# OGX360I-2CH.net
KiCad netlist of a schematic drawn in EAGLE
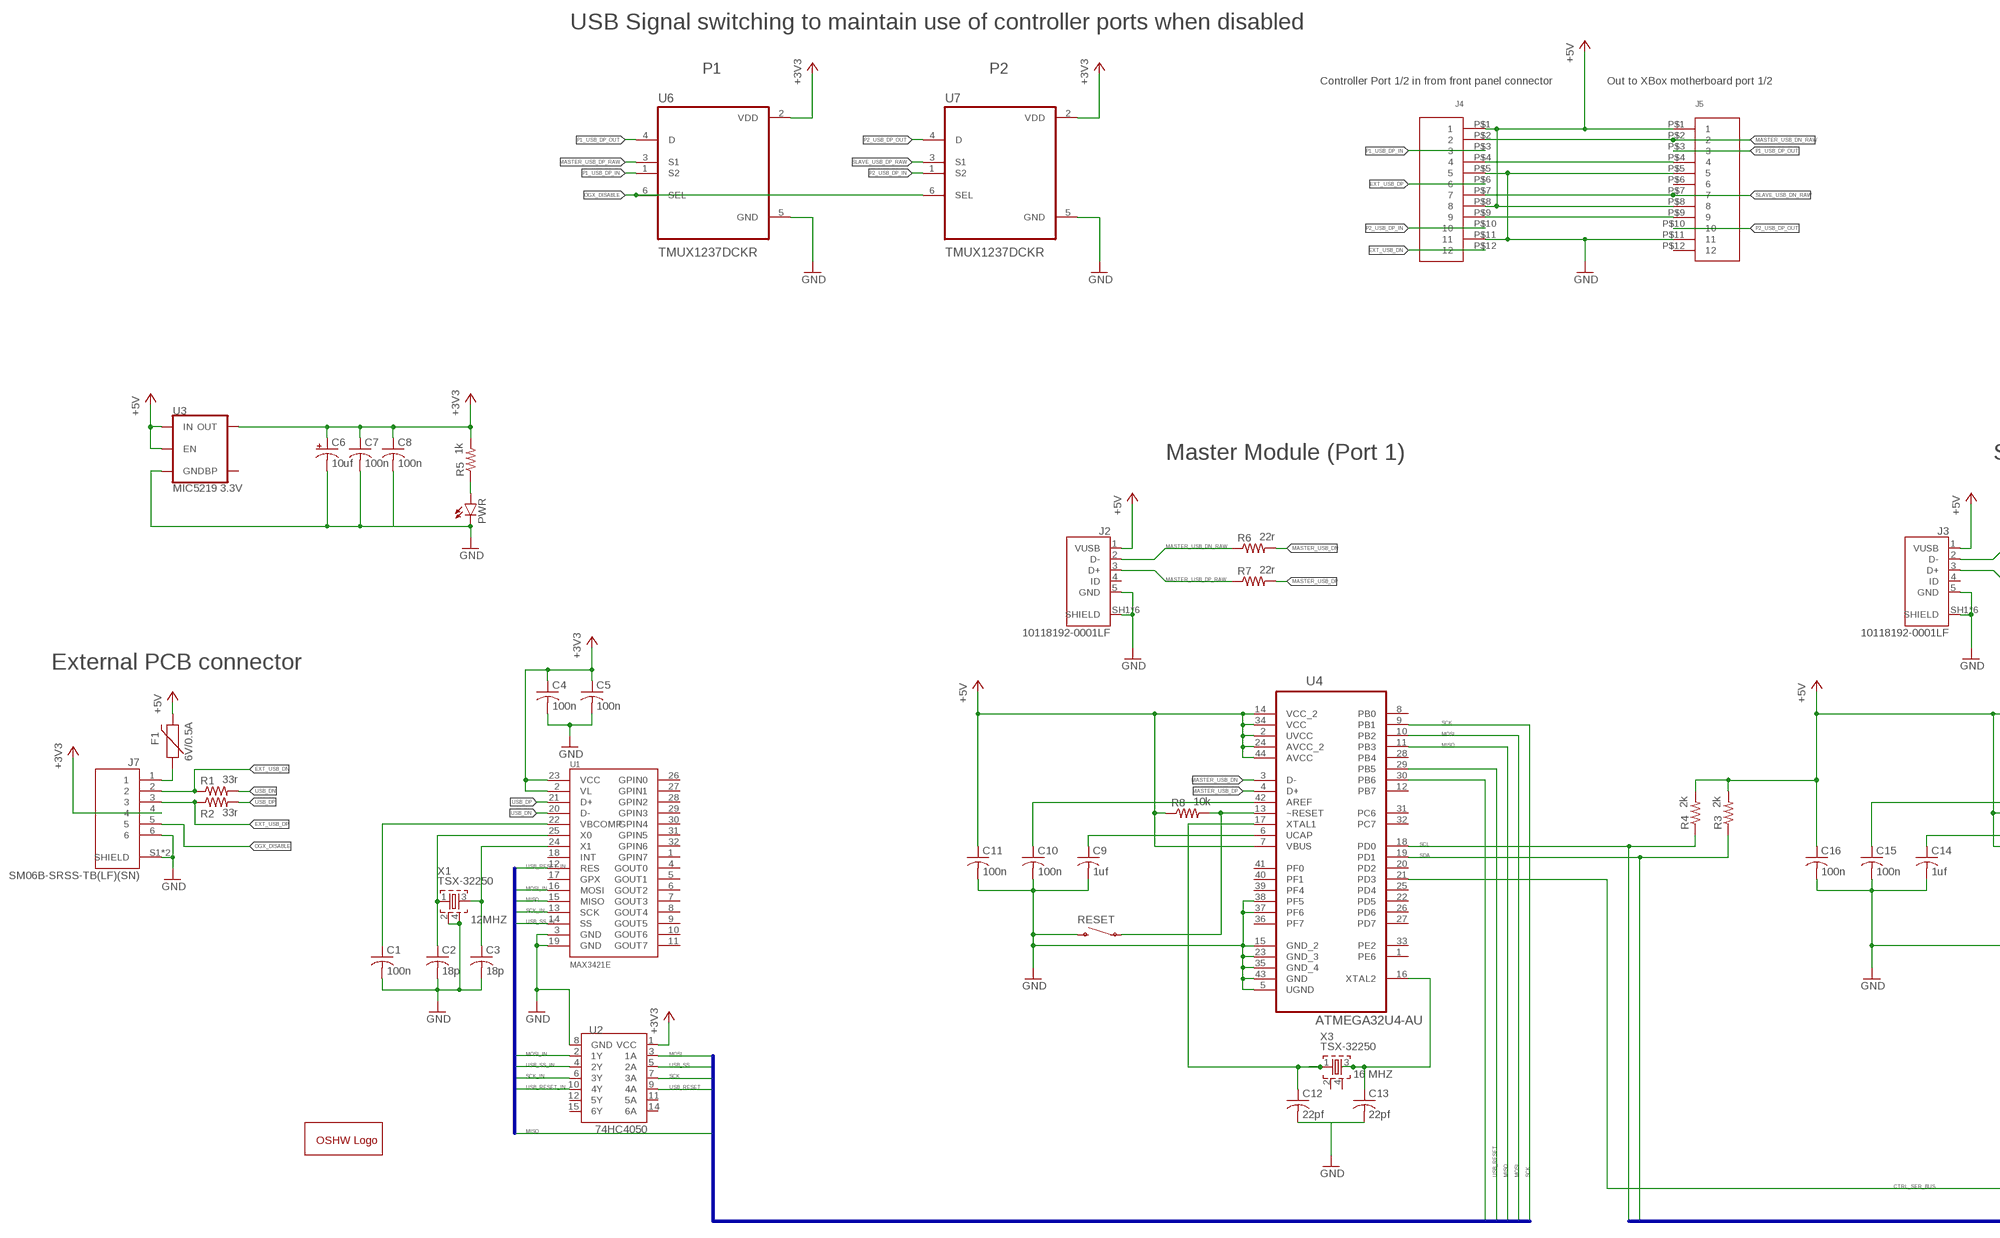
[diagram p0: schematic, sheet 1, part 1 of 2]
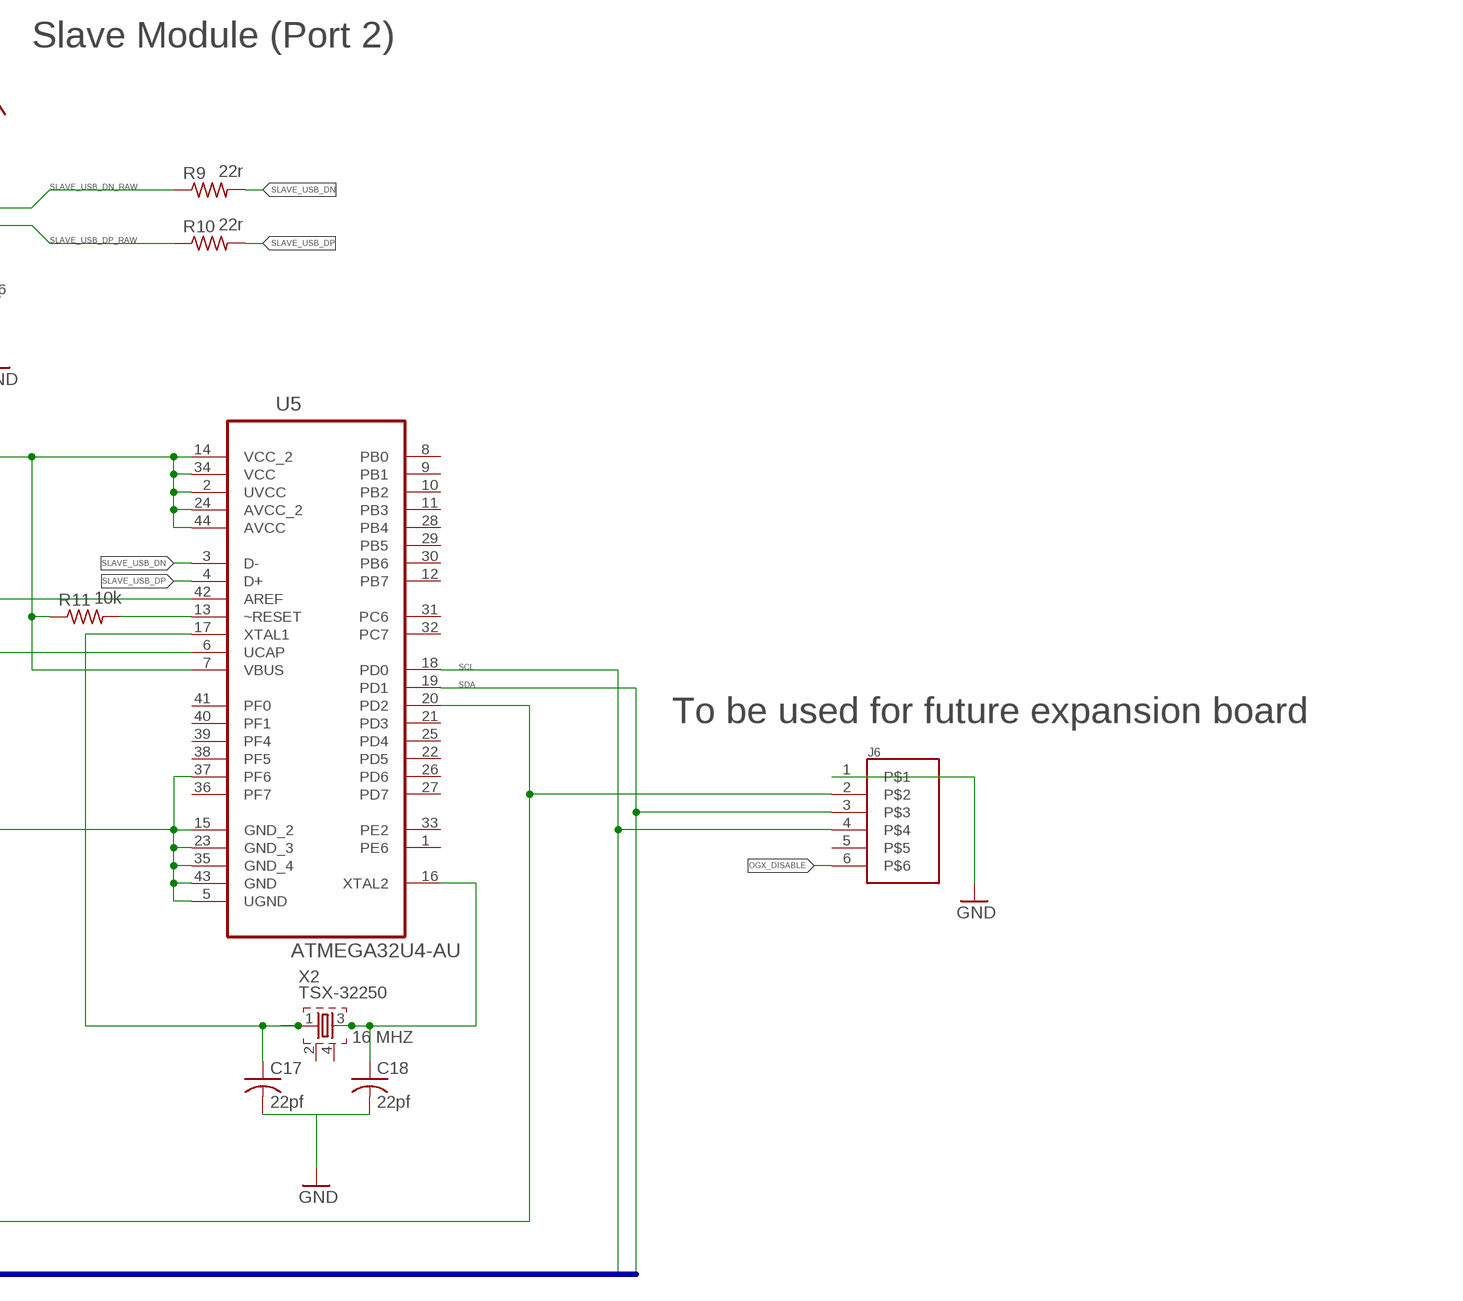
[diagram p1: schematic, sheet 1, part 2 of 2]

(export (version "E")
  (design (tool "Eeschema 10.0.6"))
  (components
    (comp (ref "C1")
      (value "100n")
      (footprint "eagle-import:C0805")
      (libsource (lib "eagle-import") (part "C-USC0805"))
    )
    (comp (ref "C2")
      (value "18p")
      (footprint "eagle-import:C0805")
      (libsource (lib "eagle-import") (part "C-USC0805"))
    )
    (comp (ref "C3")
      (value "18p")
      (footprint "eagle-import:C0805")
      (libsource (lib "eagle-import") (part "C-USC0805"))
    )
    (comp (ref "C4")
      (value "100n")
      (footprint "eagle-import:C0805")
      (libsource (lib "eagle-import") (part "C-USC0805"))
    )
    (comp (ref "C5")
      (value "100n")
      (footprint "eagle-import:C0805")
      (libsource (lib "eagle-import") (part "C-USC0805"))
    )
    (comp (ref "C6")
      (value "10uf")
      (footprint "eagle-import:153CLV-0405")
      (libsource (lib "eagle-import") (part "CPOL-US153CLV-0405"))
    )
    (comp (ref "C7")
      (value "100n")
      (footprint "eagle-import:C0805")
      (libsource (lib "eagle-import") (part "C-USC0805"))
    )
    (comp (ref "C8")
      (value "100n")
      (footprint "eagle-import:C0805")
      (libsource (lib "eagle-import") (part "C-USC0805"))
    )
    (comp (ref "C9")
      (value "1uf")
      (footprint "eagle-import:C0805")
      (libsource (lib "eagle-import") (part "C-USC0805"))
    )
    (comp (ref "C10")
      (value "100n")
      (footprint "eagle-import:C0805")
      (libsource (lib "eagle-import") (part "C-USC0805"))
    )
    (comp (ref "C11")
      (value "100n")
      (footprint "eagle-import:C0805")
      (libsource (lib "eagle-import") (part "C-USC0805"))
    )
    (comp (ref "C12")
      (value "22pf")
      (footprint "eagle-import:C0805")
      (libsource (lib "eagle-import") (part "C-USC0805"))
    )
    (comp (ref "C13")
      (value "22pf")
      (footprint "eagle-import:C0805")
      (libsource (lib "eagle-import") (part "C-USC0805"))
    )
    (comp (ref "C14")
      (value "1uf")
      (footprint "eagle-import:C0805")
      (libsource (lib "eagle-import") (part "C-USC0805"))
    )
    (comp (ref "C15")
      (value "100n")
      (footprint "eagle-import:C0805")
      (libsource (lib "eagle-import") (part "C-USC0805"))
    )
    (comp (ref "C16")
      (value "100n")
      (footprint "eagle-import:C0805")
      (libsource (lib "eagle-import") (part "C-USC0805"))
    )
    (comp (ref "C17")
      (value "22pf")
      (footprint "eagle-import:C0805")
      (libsource (lib "eagle-import") (part "C-USC0805"))
    )
    (comp (ref "C18")
      (value "22pf")
      (footprint "eagle-import:C0805")
      (libsource (lib "eagle-import") (part "C-USC0805"))
    )
    (comp (ref "F1")
      (value "6V/0.5A")
      (footprint "eagle-import:1206")
      (libsource (lib "eagle-import") (part "PPTC_HALF-AMP"))
    )
    (comp (ref "GOLD_ORB_SM1")
      (value "OSHWLOGOLOGO8MM")
      (footprint "eagle-import:OSHW_8MM")
      (libsource (lib "eagle-import") (part "OSHWLOGOLOGO8MM"))
    )
    (comp (ref "J2")
      (value "10118192-0001LF")
      (footprint "eagle-import:AMPHENOL_10118192-0001LF")
      (fields (field (name "MF") "Amphenol ICC (FCI)"))
      (libsource (lib "eagle-import") (part "10118192-0001LF"))
    )
    (comp (ref "J3")
      (value "10118192-0001LF")
      (footprint "eagle-import:AMPHENOL_10118192-0001LF")
      (fields (field (name "MF") "Amphenol ICC (FCI)"))
      (libsource (lib "eagle-import") (part "10118192-0001LF"))
    )
    (comp (ref "J4")
      (value "B12B-PHDSS")
      (footprint "eagle-import:B12B-PHDSS")
      (libsource (lib "eagle-import") (part "B12B-PHDSS"))
    )
    (comp (ref "J5")
      (value "B12B-PHDSS")
      (footprint "eagle-import:B12B-PHDSS")
      (libsource (lib "eagle-import") (part "B12B-PHDSS"))
    )
    (comp (ref "J6")
      (value "B6B-PH-K-S")
      (footprint "eagle-import:B6B-PH-K")
      (libsource (lib "eagle-import") (part "B6B-PH-K-S"))
    )
    (comp (ref "J7")
      (value "SM06B-SRSS-TB(LF)(SN)")
      (footprint "eagle-import:JST_SM06B-SRSS-TB(LF)(SN)")
      (fields
        (field (name "DIGI-KEY_PART_NUMBER") "455-1806-1-ND")
        (field (name "MF") "JST Sales")
        (field (name "MP") "SM06B-SRSS-TB_LF__SN_")
      )
      (libsource (lib "eagle-import") (part "SM06B-SRSS-TB(LF)(SN)"))
    )
    (comp (ref "PWR")
      (value "LEDCHIP-LED0805")
      (footprint "eagle-import:CHIP-LED0805")
      (libsource (lib "eagle-import") (part "LEDCHIP-LED0805"))
    )
    (comp (ref "R1")
      (value "33r")
      (footprint "eagle-import:M0805")
      (libsource (lib "eagle-import") (part "R-US_M0805"))
    )
    (comp (ref "R2")
      (value "33r")
      (footprint "eagle-import:M0805")
      (libsource (lib "eagle-import") (part "R-US_M0805"))
    )
    (comp (ref "R3")
      (value "2k")
      (footprint "eagle-import:M0805")
      (libsource (lib "eagle-import") (part "R-US_M0805"))
    )
    (comp (ref "R4")
      (value "2k")
      (footprint "eagle-import:M0805")
      (libsource (lib "eagle-import") (part "R-US_M0805"))
    )
    (comp (ref "R5")
      (value "1k")
      (footprint "eagle-import:M0805")
      (libsource (lib "eagle-import") (part "R-US_M0805"))
    )
    (comp (ref "R6")
      (value "22r")
      (footprint "eagle-import:M0805")
      (libsource (lib "eagle-import") (part "R-US_M0805"))
    )
    (comp (ref "R7")
      (value "22r")
      (footprint "eagle-import:M0805")
      (libsource (lib "eagle-import") (part "R-US_M0805"))
    )
    (comp (ref "R8")
      (value "10k")
      (footprint "eagle-import:M0805")
      (libsource (lib "eagle-import") (part "R-US_M0805"))
    )
    (comp (ref "R9")
      (value "22r")
      (footprint "eagle-import:M0805")
      (libsource (lib "eagle-import") (part "R-US_M0805"))
    )
    (comp (ref "R10")
      (value "22r")
      (footprint "eagle-import:M0805")
      (libsource (lib "eagle-import") (part "R-US_M0805"))
    )
    (comp (ref "R11")
      (value "10k")
      (footprint "eagle-import:M0805")
      (libsource (lib "eagle-import") (part "R-US_M0805"))
    )
    (comp (ref "RESET")
      (value "TL3305AF160QG")
      (footprint "eagle-import:TL3305AF160QG")
      (libsource (lib "eagle-import") (part "TL3305AF160QG"))
    )
    (comp (ref "U1")
      (value "MAX3421E")
      (footprint "eagle-import:TQFP32-5MM")
      (fields (field (name "MF") "Maxim Integrated"))
      (libsource (lib "eagle-import") (part "MAX3421E"))
    )
    (comp (ref "U2")
      (value "74HC4050")
      (footprint "eagle-import:SO16")
      (libsource (lib "eagle-import") (part "HEX_CONVERTER"))
    )
    (comp (ref "U3")
      (value "MIC5219 3.3V")
      (footprint "eagle-import:SOT23-5")
      (libsource (lib "eagle-import") (part "V_REG_MIC52193.3V"))
    )
    (comp (ref "U4")
      (value "ATMEGA32U4-AU")
      (footprint "eagle-import:QFP80P1200X1200X120-44N")
      (fields (field (name "MF") "Microchip"))
      (libsource (lib "eagle-import") (part "ATMEGA32U4-AU"))
    )
    (comp (ref "U5")
      (value "ATMEGA32U4-AU")
      (footprint "eagle-import:QFP80P1200X1200X120-44N")
      (fields (field (name "MF") "Microchip"))
      (libsource (lib "eagle-import") (part "ATMEGA32U4-AU"))
    )
    (comp (ref "U6")
      (value "TMUX1237DCKR")
      (footprint "eagle-import:SOT65P210X110-6N")
      (fields (field (name "MF") "Texas Instruments"))
      (libsource (lib "eagle-import") (part "TMUX1237DCKR"))
    )
    (comp (ref "U7")
      (value "TMUX1237DCKR")
      (footprint "eagle-import:SOT65P210X110-6N")
      (fields (field (name "MF") "Texas Instruments"))
      (libsource (lib "eagle-import") (part "TMUX1237DCKR"))
    )
    (comp (ref "X1")
      (value "TSX-32250")
      (footprint "eagle-import:TSX-3225")
      (fields
        (field (name "DIGI-KEY_PART_NUMBER") "SER4180CT-ND")
        (field (name "MF") "EPSON")
        (field (name "MP") "TSX-3225")
      )
      (libsource (lib "eagle-import") (part "TSX-32250"))
    )
    (comp (ref "X2")
      (value "TSX-32250")
      (footprint "eagle-import:TSX-3225")
      (fields
        (field (name "DIGI-KEY_PART_NUMBER") "SER4180CT-ND")
        (field (name "MF") "EPSON")
        (field (name "MP") "TSX-3225")
      )
      (libsource (lib "eagle-import") (part "TSX-32250"))
    )
    (comp (ref "X3")
      (value "TSX-32250")
      (footprint "eagle-import:TSX-3225")
      (fields
        (field (name "DIGI-KEY_PART_NUMBER") "SER4180CT-ND")
        (field (name "MF") "EPSON")
        (field (name "MP") "TSX-3225")
      )
      (libsource (lib "eagle-import") (part "TSX-32250"))
    )
  )
  (nets
    (net (code "1") (name "+3V3") (class "Default")
      (node (ref "C4") (pin "1") (pinfunction "1_1") (pintype "passive"))
      (node (ref "C5") (pin "1") (pinfunction "1_1") (pintype "passive"))
      (node (ref "C6") (pin "+") (pinfunction "+_+") (pintype "passive"))
      (node (ref "C7") (pin "1") (pinfunction "1_1") (pintype "passive"))
      (node (ref "C8") (pin "1") (pinfunction "1_1") (pintype "passive"))
      (node (ref "J7") (pin "4") (pinfunction "4_4") (pintype "passive"))
      (node (ref "R5") (pin "2") (pinfunction "2_2") (pintype "passive"))
      (node (ref "U1") (pin "2") (pinfunction "VL_2") (pintype "bidirectional"))
      (node (ref "U1") (pin "23") (pinfunction "VCC_23") (pintype "bidirectional"))
      (node (ref "U2") (pin "1") (pinfunction "VCC_1") (pintype "bidirectional"))
      (node (ref "U3") (pin "5") (pinfunction "OUT_5") (pintype "passive"))
      (node (ref "U6") (pin "2") (pinfunction "VDD_2") (pintype "power_in"))
      (node (ref "U7") (pin "2") (pinfunction "VDD_2") (pintype "power_in"))
    )
    (net (code "2") (name "+5V") (class "Default")
      (node (ref "C11") (pin "1") (pinfunction "1_1") (pintype "passive"))
      (node (ref "C16") (pin "1") (pinfunction "1_1") (pintype "passive"))
      (node (ref "F1") (pin "2") (pinfunction "2_2") (pintype "bidirectional"))
      (node (ref "J2") (pin "1") (pinfunction "VUSB_1") (pintype "passive"))
      (node (ref "J3") (pin "1") (pinfunction "VUSB_1") (pintype "passive"))
      (node (ref "J4") (pin "P$1") (pinfunction "1_P$1") (pintype "bidirectional"))
      (node (ref "J4") (pin "P$8") (pinfunction "8_P$8") (pintype "bidirectional"))
      (node (ref "J5") (pin "P$1") (pinfunction "1_P$1") (pintype "bidirectional"))
      (node (ref "J5") (pin "P$8") (pinfunction "8_P$8") (pintype "bidirectional"))
      (node (ref "R11") (pin "1") (pinfunction "1_1") (pintype "passive"))
      (node (ref "R3") (pin "2") (pinfunction "2_2") (pintype "passive"))
      (node (ref "R4") (pin "2") (pinfunction "2_2") (pintype "passive"))
      (node (ref "R8") (pin "1") (pinfunction "1_1") (pintype "passive"))
      (node (ref "U3") (pin "1") (pinfunction "IN_1") (pintype "input"))
      (node (ref "U3") (pin "3") (pinfunction "EN_3") (pintype "input"))
      (node (ref "U4") (pin "14") (pinfunction "VCC_2_14") (pintype "power_in"))
      (node (ref "U4") (pin "2") (pinfunction "UVCC_2") (pintype "power_in"))
      (node (ref "U4") (pin "24") (pinfunction "AVCC_2_24") (pintype "power_in"))
      (node (ref "U4") (pin "34") (pinfunction "VCC_34") (pintype "power_in"))
      (node (ref "U4") (pin "44") (pinfunction "AVCC_44") (pintype "power_in"))
      (node (ref "U4") (pin "7") (pinfunction "VBUS_7") (pintype "input"))
      (node (ref "U5") (pin "14") (pinfunction "VCC_2_14") (pintype "power_in"))
      (node (ref "U5") (pin "2") (pinfunction "UVCC_2") (pintype "power_in"))
      (node (ref "U5") (pin "24") (pinfunction "AVCC_2_24") (pintype "power_in"))
      (node (ref "U5") (pin "34") (pinfunction "VCC_34") (pintype "power_in"))
      (node (ref "U5") (pin "44") (pinfunction "AVCC_44") (pintype "power_in"))
      (node (ref "U5") (pin "7") (pinfunction "VBUS_7") (pintype "input"))
    )
    (net (code "3") (name "/CTRL_SER_BUS") (class "Default")
      (node (ref "J6") (pin "2") (pinfunction "P$2_2") (pintype "bidirectional"))
      (node (ref "U4") (pin "21") (pinfunction "PD3_21") (pintype "bidirectional"))
      (node (ref "U5") (pin "20") (pinfunction "PD2_20") (pintype "bidirectional"))
    )
    (net (code "4") (name "/MISO") (class "Default")
      (node (ref "U1") (pin "15") (pinfunction "MISO_15") (pintype "bidirectional"))
      (node (ref "U4") (pin "11") (pinfunction "PB3_11") (pintype "bidirectional"))
    )
    (net (code "5") (name "/MOSI") (class "Default")
      (node (ref "U2") (pin "3") (pinfunction "1A_3") (pintype "bidirectional"))
      (node (ref "U4") (pin "10") (pinfunction "PB2_10") (pintype "bidirectional"))
    )
    (net (code "6") (name "/MOSI_IN") (class "Default")
      (node (ref "U1") (pin "16") (pinfunction "MOSI_16") (pintype "bidirectional"))
      (node (ref "U2") (pin "2") (pinfunction "1Y_2") (pintype "bidirectional"))
    )
    (net (code "7") (name "/RESET") (class "Default")
      (node (ref "R11") (pin "2") (pinfunction "2_2") (pintype "passive"))
      (node (ref "R8") (pin "2") (pinfunction "2_2") (pintype "passive"))
      (node (ref "RESET") (pin "P$3") (pinfunction "2_P$3") (pintype "bidirectional"))
      (node (ref "RESET") (pin "P$4") (pinfunction "2_P$4") (pintype "bidirectional"))
      (node (ref "U4") (pin "13") (pinfunction "~{RESET}_13") (pintype "input"))
      (node (ref "U5") (pin "13") (pinfunction "~{RESET}_13") (pintype "input"))
    )
    (net (code "8") (name "/SCK") (class "Default")
      (node (ref "U2") (pin "7") (pinfunction "3A_7") (pintype "bidirectional"))
      (node (ref "U4") (pin "9") (pinfunction "PB1_9") (pintype "bidirectional"))
    )
    (net (code "9") (name "/SCK_IN") (class "Default")
      (node (ref "U1") (pin "13") (pinfunction "SCK_13") (pintype "bidirectional"))
      (node (ref "U2") (pin "6") (pinfunction "3Y_6") (pintype "bidirectional"))
    )
    (net (code "10") (name "/SCL") (class "Default")
      (node (ref "J6") (pin "4") (pinfunction "P$4_4") (pintype "bidirectional"))
      (node (ref "R4") (pin "1") (pinfunction "1_1") (pintype "passive"))
      (node (ref "U4") (pin "18") (pinfunction "PD0_18") (pintype "bidirectional"))
      (node (ref "U5") (pin "18") (pinfunction "PD0_18") (pintype "bidirectional"))
    )
    (net (code "11") (name "/SDA") (class "Default")
      (node (ref "J6") (pin "3") (pinfunction "P$3_3") (pintype "bidirectional"))
      (node (ref "R3") (pin "1") (pinfunction "1_1") (pintype "passive"))
      (node (ref "U4") (pin "19") (pinfunction "PD1_19") (pintype "bidirectional"))
      (node (ref "U5") (pin "19") (pinfunction "PD1_19") (pintype "bidirectional"))
    )
    (net (code "12") (name "/USB_RESET") (class "Default")
      (node (ref "U2") (pin "9") (pinfunction "4A_9") (pintype "bidirectional"))
      (node (ref "U4") (pin "29") (pinfunction "PB5_29") (pintype "bidirectional"))
    )
    (net (code "13") (name "/USB_RESET_IN") (class "Default")
      (node (ref "U1") (pin "12") (pinfunction "RES_12") (pintype "bidirectional"))
      (node (ref "U2") (pin "10") (pinfunction "4Y_10") (pintype "bidirectional"))
    )
    (net (code "14") (name "/USB_SS") (class "Default")
      (node (ref "U2") (pin "5") (pinfunction "2A_5") (pintype "bidirectional"))
      (node (ref "U4") (pin "30") (pinfunction "PB6_30") (pintype "bidirectional"))
    )
    (net (code "15") (name "/USB_SS_IN") (class "Default")
      (node (ref "U1") (pin "14") (pinfunction "SS_14") (pintype "bidirectional"))
      (node (ref "U2") (pin "4") (pinfunction "2Y_4") (pintype "bidirectional"))
    )
    (net (code "16") (name "EXT_USB_DN") (class "Default")
      (node (ref "J4") (pin "P$12") (pinfunction "12_P$12") (pintype "bidirectional"))
      (node (ref "J7") (pin "2") (pinfunction "2_2") (pintype "passive"))
      (node (ref "R1") (pin "1") (pinfunction "1_1") (pintype "passive"))
    )
    (net (code "17") (name "EXT_USB_DP") (class "Default")
      (node (ref "J4") (pin "P$6") (pinfunction "6_P$6") (pintype "bidirectional"))
      (node (ref "J7") (pin "3") (pinfunction "3_3") (pintype "passive"))
      (node (ref "R2") (pin "1") (pinfunction "1_1") (pintype "passive"))
    )
    (net (code "18") (name "GND") (class "Default")
      (node (ref "C1") (pin "2") (pinfunction "2_2") (pintype "passive"))
      (node (ref "C10") (pin "2") (pinfunction "2_2") (pintype "passive"))
      (node (ref "C11") (pin "2") (pinfunction "2_2") (pintype "passive"))
      (node (ref "C12") (pin "2") (pinfunction "2_2") (pintype "passive"))
      (node (ref "C13") (pin "2") (pinfunction "2_2") (pintype "passive"))
      (node (ref "C14") (pin "2") (pinfunction "2_2") (pintype "passive"))
      (node (ref "C15") (pin "2") (pinfunction "2_2") (pintype "passive"))
      (node (ref "C16") (pin "2") (pinfunction "2_2") (pintype "passive"))
      (node (ref "C17") (pin "2") (pinfunction "2_2") (pintype "passive"))
      (node (ref "C18") (pin "2") (pinfunction "2_2") (pintype "passive"))
      (node (ref "C2") (pin "2") (pinfunction "2_2") (pintype "passive"))
      (node (ref "C3") (pin "2") (pinfunction "2_2") (pintype "passive"))
      (node (ref "C4") (pin "2") (pinfunction "2_2") (pintype "passive"))
      (node (ref "C5") (pin "2") (pinfunction "2_2") (pintype "passive"))
      (node (ref "C6") (pin "-") (pinfunction "-_-") (pintype "passive"))
      (node (ref "C7") (pin "2") (pinfunction "2_2") (pintype "passive"))
      (node (ref "C8") (pin "2") (pinfunction "2_2") (pintype "passive"))
      (node (ref "C9") (pin "2") (pinfunction "2_2") (pintype "passive"))
      (node (ref "J2") (pin "5") (pinfunction "GND_5") (pintype "passive"))
      (node (ref "J2") (pin "SH1") (pinfunction "SHIELD_SH1") (pintype "passive"))
      (node (ref "J2") (pin "SH2") (pinfunction "SHIELD_SH2") (pintype "passive"))
      (node (ref "J2") (pin "SH3") (pinfunction "SHIELD_SH3") (pintype "passive"))
      (node (ref "J2") (pin "SH4") (pinfunction "SHIELD_SH4") (pintype "passive"))
      (node (ref "J2") (pin "SH5") (pinfunction "SHIELD_SH5") (pintype "passive"))
      (node (ref "J2") (pin "SH6") (pinfunction "SHIELD_SH6") (pintype "passive"))
      (node (ref "J3") (pin "5") (pinfunction "GND_5") (pintype "passive"))
      (node (ref "J3") (pin "SH1") (pinfunction "SHIELD_SH1") (pintype "passive"))
      (node (ref "J3") (pin "SH2") (pinfunction "SHIELD_SH2") (pintype "passive"))
      (node (ref "J3") (pin "SH3") (pinfunction "SHIELD_SH3") (pintype "passive"))
      (node (ref "J3") (pin "SH4") (pinfunction "SHIELD_SH4") (pintype "passive"))
      (node (ref "J3") (pin "SH5") (pinfunction "SHIELD_SH5") (pintype "passive"))
      (node (ref "J3") (pin "SH6") (pinfunction "SHIELD_SH6") (pintype "passive"))
      (node (ref "J4") (pin "P$11") (pinfunction "11_P$11") (pintype "bidirectional"))
      (node (ref "J4") (pin "P$5") (pinfunction "5_P$5") (pintype "bidirectional"))
      (node (ref "J5") (pin "P$11") (pinfunction "11_P$11") (pintype "bidirectional"))
      (node (ref "J5") (pin "P$5") (pinfunction "5_P$5") (pintype "bidirectional"))
      (node (ref "J6") (pin "1") (pinfunction "P$1_1") (pintype "bidirectional"))
      (node (ref "J7") (pin "6") (pinfunction "6_6") (pintype "passive"))
      (node (ref "J7") (pin "S1") (pinfunction "SHIELD_S1") (pintype "passive"))
      (node (ref "J7") (pin "S2") (pinfunction "SHIELD_S2") (pintype "passive"))
      (node (ref "PWR") (pin "C") (pinfunction "C_C") (pintype "passive"))
      (node (ref "RESET") (pin "P$1") (pinfunction "P$1_P$1") (pintype "bidirectional"))
      (node (ref "RESET") (pin "P$2") (pinfunction "P$1_P$2") (pintype "bidirectional"))
      (node (ref "U1") (pin "19") (pinfunction "GND_19") (pintype "bidirectional"))
      (node (ref "U1") (pin "3") (pinfunction "GND_3") (pintype "bidirectional"))
      (node (ref "U2") (pin "8") (pinfunction "GND_8") (pintype "bidirectional"))
      (node (ref "U3") (pin "2") (pinfunction "GND_2") (pintype "input"))
      (node (ref "U4") (pin "15") (pinfunction "GND_2_15") (pintype "passive"))
      (node (ref "U4") (pin "23") (pinfunction "GND_3_23") (pintype "passive"))
      (node (ref "U4") (pin "35") (pinfunction "GND_4_35") (pintype "passive"))
      (node (ref "U4") (pin "37") (pinfunction "PF6_37") (pintype "bidirectional"))
      (node (ref "U4") (pin "38") (pinfunction "PF5_38") (pintype "bidirectional"))
      (node (ref "U4") (pin "43") (pinfunction "GND_43") (pintype "passive"))
      (node (ref "U4") (pin "5") (pinfunction "UGND_5") (pintype "passive"))
      (node (ref "U5") (pin "15") (pinfunction "GND_2_15") (pintype "passive"))
      (node (ref "U5") (pin "23") (pinfunction "GND_3_23") (pintype "passive"))
      (node (ref "U5") (pin "35") (pinfunction "GND_4_35") (pintype "passive"))
      (node (ref "U5") (pin "37") (pinfunction "PF6_37") (pintype "bidirectional"))
      (node (ref "U5") (pin "43") (pinfunction "GND_43") (pintype "passive"))
      (node (ref "U5") (pin "5") (pinfunction "UGND_5") (pintype "passive"))
      (node (ref "U6") (pin "5") (pinfunction "GND_5") (pintype "power_in"))
      (node (ref "U7") (pin "5") (pinfunction "GND_5") (pintype "power_in"))
      (node (ref "X1") (pin "2") (pinfunction "2_2") (pintype "passive"))
      (node (ref "X1") (pin "4") (pinfunction "4_4") (pintype "passive"))
    )
    (net (code "19") (name "MASTER_USB_DN") (class "Default")
      (node (ref "R6") (pin "2") (pinfunction "2_2") (pintype "passive"))
      (node (ref "U4") (pin "3") (pinfunction "D-_3") (pintype "passive"))
    )
    (net (code "20") (name "MASTER_USB_DN_RAW") (class "Default")
      (node (ref "J2") (pin "2") (pinfunction "D-_2") (pintype "passive"))
      (node (ref "J4") (pin "P$2") (pinfunction "2_P$2") (pintype "bidirectional"))
      (node (ref "J5") (pin "P$2") (pinfunction "2_P$2") (pintype "bidirectional"))
      (node (ref "R6") (pin "1") (pinfunction "1_1") (pintype "passive"))
    )
    (net (code "21") (name "MASTER_USB_DP") (class "Default")
      (node (ref "R7") (pin "2") (pinfunction "2_2") (pintype "passive"))
      (node (ref "U4") (pin "4") (pinfunction "D+_4") (pintype "passive"))
    )
    (net (code "22") (name "MASTER_USB_DP_RAW") (class "Default")
      (node (ref "J2") (pin "3") (pinfunction "D+_3") (pintype "passive"))
      (node (ref "R7") (pin "1") (pinfunction "1_1") (pintype "passive"))
      (node (ref "U6") (pin "3") (pinfunction "S1_3") (pintype "bidirectional"))
    )
    (net (code "23") (name "Net-(F1-Pad1)") (class "Default")
      (node (ref "F1") (pin "1") (pinfunction "1_1") (pintype "bidirectional"))
      (node (ref "J7") (pin "1") (pinfunction "1_1") (pintype "passive"))
    )
    (net (code "24") (name "Net-(J4-4)") (class "Default")
      (node (ref "J4") (pin "P$4") (pinfunction "4_P$4") (pintype "bidirectional"))
      (node (ref "J5") (pin "P$4") (pinfunction "4_P$4") (pintype "bidirectional"))
    )
    (net (code "25") (name "Net-(J4-9)") (class "Default")
      (node (ref "J4") (pin "P$9") (pinfunction "9_P$9") (pintype "bidirectional"))
      (node (ref "J5") (pin "P$9") (pinfunction "9_P$9") (pintype "bidirectional"))
    )
    (net (code "26") (name "Net-(PWR-PadA)") (class "Default")
      (node (ref "PWR") (pin "A") (pinfunction "A_A") (pintype "passive"))
      (node (ref "R5") (pin "1") (pinfunction "1_1") (pintype "passive"))
    )
    (net (code "27") (name "Net-(U1-VBCOMP)") (class "Default")
      (node (ref "C1") (pin "1") (pinfunction "1_1") (pintype "passive"))
      (node (ref "U1") (pin "22") (pinfunction "VBCOMP_22") (pintype "bidirectional"))
    )
    (net (code "28") (name "Net-(U1-X0)") (class "Default")
      (node (ref "C2") (pin "1") (pinfunction "1_1") (pintype "passive"))
      (node (ref "U1") (pin "25") (pinfunction "X0_25") (pintype "bidirectional"))
      (node (ref "X1") (pin "1") (pinfunction "1_1") (pintype "passive"))
    )
    (net (code "29") (name "Net-(U1-X1)") (class "Default")
      (node (ref "C3") (pin "1") (pinfunction "1_1") (pintype "passive"))
      (node (ref "U1") (pin "24") (pinfunction "X1_24") (pintype "bidirectional"))
      (node (ref "X1") (pin "3") (pinfunction "3_3") (pintype "passive"))
    )
    (net (code "30") (name "Net-(U4-AREF)") (class "Default")
      (node (ref "C10") (pin "1") (pinfunction "1_1") (pintype "passive"))
      (node (ref "U4") (pin "42") (pinfunction "AREF_42") (pintype "input"))
    )
    (net (code "31") (name "Net-(U4-UCAP)") (class "Default")
      (node (ref "C9") (pin "1") (pinfunction "1_1") (pintype "passive"))
      (node (ref "U4") (pin "6") (pinfunction "UCAP_6") (pintype "power_in"))
    )
    (net (code "32") (name "Net-(U4-XTAL1)") (class "Default")
      (node (ref "C12") (pin "1") (pinfunction "1_1") (pintype "passive"))
      (node (ref "U4") (pin "17") (pinfunction "XTAL1_17") (pintype "input"))
      (node (ref "X3") (pin "1") (pinfunction "1_1") (pintype "passive"))
    )
    (net (code "33") (name "Net-(U4-XTAL2)") (class "Default")
      (node (ref "C13") (pin "1") (pinfunction "1_1") (pintype "passive"))
      (node (ref "U4") (pin "16") (pinfunction "XTAL2_16") (pintype "output"))
      (node (ref "X3") (pin "3") (pinfunction "3_3") (pintype "passive"))
    )
    (net (code "34") (name "Net-(U5-AREF)") (class "Default")
      (node (ref "C15") (pin "1") (pinfunction "1_1") (pintype "passive"))
      (node (ref "U5") (pin "42") (pinfunction "AREF_42") (pintype "input"))
    )
    (net (code "35") (name "Net-(U5-UCAP)") (class "Default")
      (node (ref "C14") (pin "1") (pinfunction "1_1") (pintype "passive"))
      (node (ref "U5") (pin "6") (pinfunction "UCAP_6") (pintype "power_in"))
    )
    (net (code "36") (name "Net-(U5-XTAL1)") (class "Default")
      (node (ref "C17") (pin "1") (pinfunction "1_1") (pintype "passive"))
      (node (ref "U5") (pin "17") (pinfunction "XTAL1_17") (pintype "input"))
      (node (ref "X2") (pin "1") (pinfunction "1_1") (pintype "passive"))
    )
    (net (code "37") (name "Net-(U5-XTAL2)") (class "Default")
      (node (ref "C18") (pin "1") (pinfunction "1_1") (pintype "passive"))
      (node (ref "U5") (pin "16") (pinfunction "XTAL2_16") (pintype "output"))
      (node (ref "X2") (pin "3") (pinfunction "3_3") (pintype "passive"))
    )
    (net (code "38") (name "OGX_DISABLE") (class "Default")
      (node (ref "J6") (pin "6") (pinfunction "P$6_6") (pintype "bidirectional"))
      (node (ref "J7") (pin "5") (pinfunction "5_5") (pintype "passive"))
      (node (ref "U6") (pin "6") (pinfunction "SEL_6") (pintype "bidirectional"))
      (node (ref "U7") (pin "6") (pinfunction "SEL_6") (pintype "bidirectional"))
    )
    (net (code "39") (name "P1_USB_DP_IN") (class "Default")
      (node (ref "J4") (pin "P$3") (pinfunction "3_P$3") (pintype "bidirectional"))
      (node (ref "U6") (pin "1") (pinfunction "S2_1") (pintype "bidirectional"))
    )
    (net (code "40") (name "P1_USB_DP_OUT") (class "Default")
      (node (ref "J5") (pin "P$3") (pinfunction "3_P$3") (pintype "bidirectional"))
      (node (ref "U6") (pin "4") (pinfunction "D_4") (pintype "bidirectional"))
    )
    (net (code "41") (name "P2_USB_DP_IN") (class "Default")
      (node (ref "J4") (pin "P$10") (pinfunction "10_P$10") (pintype "bidirectional"))
      (node (ref "U7") (pin "1") (pinfunction "S2_1") (pintype "bidirectional"))
    )
    (net (code "42") (name "P2_USB_DP_OUT") (class "Default")
      (node (ref "J5") (pin "P$10") (pinfunction "10_P$10") (pintype "bidirectional"))
      (node (ref "U7") (pin "4") (pinfunction "D_4") (pintype "bidirectional"))
    )
    (net (code "43") (name "SLAVE_USB_DN") (class "Default")
      (node (ref "R9") (pin "2") (pinfunction "2_2") (pintype "passive"))
      (node (ref "U5") (pin "3") (pinfunction "D-_3") (pintype "passive"))
    )
    (net (code "44") (name "SLAVE_USB_DN_RAW") (class "Default")
      (node (ref "J3") (pin "2") (pinfunction "D-_2") (pintype "passive"))
      (node (ref "J4") (pin "P$7") (pinfunction "7_P$7") (pintype "bidirectional"))
      (node (ref "J5") (pin "P$7") (pinfunction "7_P$7") (pintype "bidirectional"))
      (node (ref "R9") (pin "1") (pinfunction "1_1") (pintype "passive"))
    )
    (net (code "45") (name "SLAVE_USB_DP") (class "Default")
      (node (ref "R10") (pin "2") (pinfunction "2_2") (pintype "passive"))
      (node (ref "U5") (pin "4") (pinfunction "D+_4") (pintype "passive"))
    )
    (net (code "46") (name "SLAVE_USB_DP_RAW") (class "Default")
      (node (ref "J3") (pin "3") (pinfunction "D+_3") (pintype "passive"))
      (node (ref "R10") (pin "1") (pinfunction "1_1") (pintype "passive"))
      (node (ref "U7") (pin "3") (pinfunction "S1_3") (pintype "bidirectional"))
    )
    (net (code "47") (name "USB_DN") (class "Default")
      (node (ref "R1") (pin "2") (pinfunction "2_2") (pintype "passive"))
      (node (ref "U1") (pin "20") (pinfunction "D-_20") (pintype "bidirectional"))
    )
    (net (code "48") (name "USB_DP") (class "Default")
      (node (ref "R2") (pin "2") (pinfunction "2_2") (pintype "passive"))
      (node (ref "U1") (pin "21") (pinfunction "D+_21") (pintype "bidirectional"))
    )
    (net (code "49") (name "unconnected-(J2-ID-Pad4)") (class "Default")
      (node (ref "J2") (pin "4") (pinfunction "ID_4") (pintype "passive"))
    )
    (net (code "50") (name "unconnected-(J3-ID-Pad4)") (class "Default")
      (node (ref "J3") (pin "4") (pinfunction "ID_4") (pintype "passive"))
    )
    (net (code "51") (name "unconnected-(J5-6-PadP$6)") (class "Default")
      (node (ref "J5") (pin "P$6") (pinfunction "6_P$6") (pintype "bidirectional"))
    )
    (net (code "52") (name "unconnected-(J5-12-PadP$12)") (class "Default")
      (node (ref "J5") (pin "P$12") (pinfunction "12_P$12") (pintype "bidirectional"))
    )
    (net (code "53") (name "unconnected-(J6-P$5-Pad5)") (class "Default")
      (node (ref "J6") (pin "5") (pinfunction "P$5_5") (pintype "bidirectional"))
    )
    (net (code "54") (name "unconnected-(U1-GOUT0-Pad4)") (class "Default")
      (node (ref "U1") (pin "4") (pinfunction "GOUT0_4") (pintype "bidirectional"))
    )
    (net (code "55") (name "unconnected-(U1-GOUT1-Pad5)") (class "Default")
      (node (ref "U1") (pin "5") (pinfunction "GOUT1_5") (pintype "bidirectional"))
    )
    (net (code "56") (name "unconnected-(U1-GOUT2-Pad6)") (class "Default")
      (node (ref "U1") (pin "6") (pinfunction "GOUT2_6") (pintype "bidirectional"))
    )
    (net (code "57") (name "unconnected-(U1-GOUT3-Pad7)") (class "Default")
      (node (ref "U1") (pin "7") (pinfunction "GOUT3_7") (pintype "bidirectional"))
    )
    (net (code "58") (name "unconnected-(U1-GOUT4-Pad8)") (class "Default")
      (node (ref "U1") (pin "8") (pinfunction "GOUT4_8") (pintype "bidirectional"))
    )
    (net (code "59") (name "unconnected-(U1-GOUT5-Pad9)") (class "Default")
      (node (ref "U1") (pin "9") (pinfunction "GOUT5_9") (pintype "bidirectional"))
    )
    (net (code "60") (name "unconnected-(U1-GOUT6-Pad10)") (class "Default")
      (node (ref "U1") (pin "10") (pinfunction "GOUT6_10") (pintype "bidirectional"))
    )
    (net (code "61") (name "unconnected-(U1-GOUT7-Pad11)") (class "Default")
      (node (ref "U1") (pin "11") (pinfunction "GOUT7_11") (pintype "bidirectional"))
    )
    (net (code "62") (name "unconnected-(U1-GPIN0-Pad26)") (class "Default")
      (node (ref "U1") (pin "26") (pinfunction "GPIN0_26") (pintype "bidirectional"))
    )
    (net (code "63") (name "unconnected-(U1-GPIN1-Pad27)") (class "Default")
      (node (ref "U1") (pin "27") (pinfunction "GPIN1_27") (pintype "bidirectional"))
    )
    (net (code "64") (name "unconnected-(U1-GPIN2-Pad28)") (class "Default")
      (node (ref "U1") (pin "28") (pinfunction "GPIN2_28") (pintype "bidirectional"))
    )
    (net (code "65") (name "unconnected-(U1-GPIN3-Pad29)") (class "Default")
      (node (ref "U1") (pin "29") (pinfunction "GPIN3_29") (pintype "bidirectional"))
    )
    (net (code "66") (name "unconnected-(U1-GPIN4-Pad30)") (class "Default")
      (node (ref "U1") (pin "30") (pinfunction "GPIN4_30") (pintype "bidirectional"))
    )
    (net (code "67") (name "unconnected-(U1-GPIN5-Pad31)") (class "Default")
      (node (ref "U1") (pin "31") (pinfunction "GPIN5_31") (pintype "bidirectional"))
    )
    (net (code "68") (name "unconnected-(U1-GPIN6-Pad32)") (class "Default")
      (node (ref "U1") (pin "32") (pinfunction "GPIN6_32") (pintype "bidirectional"))
    )
    (net (code "69") (name "unconnected-(U1-GPIN7-Pad1)") (class "Default")
      (node (ref "U1") (pin "1") (pinfunction "GPIN7_1") (pintype "bidirectional"))
    )
    (net (code "70") (name "unconnected-(U1-GPX-Pad17)") (class "Default")
      (node (ref "U1") (pin "17") (pinfunction "GPX_17") (pintype "bidirectional"))
    )
    (net (code "71") (name "unconnected-(U1-INT-Pad18)") (class "Default")
      (node (ref "U1") (pin "18") (pinfunction "INT_18") (pintype "bidirectional"))
    )
    (net (code "72") (name "unconnected-(U2-5A-Pad11)") (class "Default")
      (node (ref "U2") (pin "11") (pinfunction "5A_11") (pintype "bidirectional"))
    )
    (net (code "73") (name "unconnected-(U2-5Y-Pad12)") (class "Default")
      (node (ref "U2") (pin "12") (pinfunction "5Y_12") (pintype "bidirectional"))
    )
    (net (code "74") (name "unconnected-(U2-6A-Pad14)") (class "Default")
      (node (ref "U2") (pin "14") (pinfunction "6A_14") (pintype "bidirectional"))
    )
    (net (code "75") (name "unconnected-(U2-6Y-Pad15)") (class "Default")
      (node (ref "U2") (pin "15") (pinfunction "6Y_15") (pintype "bidirectional"))
    )
    (net (code "76") (name "unconnected-(U3-BP-Pad4)") (class "Default")
      (node (ref "U3") (pin "4") (pinfunction "BP_4") (pintype "input"))
    )
    (net (code "77") (name "unconnected-(U4-PB0-Pad8)") (class "Default")
      (node (ref "U4") (pin "8") (pinfunction "PB0_8") (pintype "bidirectional"))
    )
    (net (code "78") (name "unconnected-(U4-PB4-Pad28)") (class "Default")
      (node (ref "U4") (pin "28") (pinfunction "PB4_28") (pintype "bidirectional"))
    )
    (net (code "79") (name "unconnected-(U4-PB7-Pad12)") (class "Default")
      (node (ref "U4") (pin "12") (pinfunction "PB7_12") (pintype "bidirectional"))
    )
    (net (code "80") (name "unconnected-(U4-PC6-Pad31)") (class "Default")
      (node (ref "U4") (pin "31") (pinfunction "PC6_31") (pintype "bidirectional"))
    )
    (net (code "81") (name "unconnected-(U4-PC7-Pad32)") (class "Default")
      (node (ref "U4") (pin "32") (pinfunction "PC7_32") (pintype "bidirectional"))
    )
    (net (code "82") (name "unconnected-(U4-PD2-Pad20)") (class "Default")
      (node (ref "U4") (pin "20") (pinfunction "PD2_20") (pintype "bidirectional"))
    )
    (net (code "83") (name "unconnected-(U4-PD4-Pad25)") (class "Default")
      (node (ref "U4") (pin "25") (pinfunction "PD4_25") (pintype "bidirectional"))
    )
    (net (code "84") (name "unconnected-(U4-PD5-Pad22)") (class "Default")
      (node (ref "U4") (pin "22") (pinfunction "PD5_22") (pintype "bidirectional"))
    )
    (net (code "85") (name "unconnected-(U4-PD6-Pad26)") (class "Default")
      (node (ref "U4") (pin "26") (pinfunction "PD6_26") (pintype "bidirectional"))
    )
    (net (code "86") (name "unconnected-(U4-PD7-Pad27)") (class "Default")
      (node (ref "U4") (pin "27") (pinfunction "PD7_27") (pintype "bidirectional"))
    )
    (net (code "87") (name "unconnected-(U4-PE2-Pad33)") (class "Default")
      (node (ref "U4") (pin "33") (pinfunction "PE2_33") (pintype "bidirectional"))
    )
    (net (code "88") (name "unconnected-(U4-PE6-Pad1)") (class "Default")
      (node (ref "U4") (pin "1") (pinfunction "PE6_1") (pintype "bidirectional"))
    )
    (net (code "89") (name "unconnected-(U4-PF0-Pad41)") (class "Default")
      (node (ref "U4") (pin "41") (pinfunction "PF0_41") (pintype "bidirectional"))
    )
    (net (code "90") (name "unconnected-(U4-PF1-Pad40)") (class "Default")
      (node (ref "U4") (pin "40") (pinfunction "PF1_40") (pintype "bidirectional"))
    )
    (net (code "91") (name "unconnected-(U4-PF4-Pad39)") (class "Default")
      (node (ref "U4") (pin "39") (pinfunction "PF4_39") (pintype "bidirectional"))
    )
    (net (code "92") (name "unconnected-(U4-PF7-Pad36)") (class "Default")
      (node (ref "U4") (pin "36") (pinfunction "PF7_36") (pintype "bidirectional"))
    )
    (net (code "93") (name "unconnected-(U5-PB0-Pad8)") (class "Default")
      (node (ref "U5") (pin "8") (pinfunction "PB0_8") (pintype "bidirectional"))
    )
    (net (code "94") (name "unconnected-(U5-PB1-Pad9)") (class "Default")
      (node (ref "U5") (pin "9") (pinfunction "PB1_9") (pintype "bidirectional"))
    )
    (net (code "95") (name "unconnected-(U5-PB2-Pad10)") (class "Default")
      (node (ref "U5") (pin "10") (pinfunction "PB2_10") (pintype "bidirectional"))
    )
    (net (code "96") (name "unconnected-(U5-PB3-Pad11)") (class "Default")
      (node (ref "U5") (pin "11") (pinfunction "PB3_11") (pintype "bidirectional"))
    )
    (net (code "97") (name "unconnected-(U5-PB4-Pad28)") (class "Default")
      (node (ref "U5") (pin "28") (pinfunction "PB4_28") (pintype "bidirectional"))
    )
    (net (code "98") (name "unconnected-(U5-PB5-Pad29)") (class "Default")
      (node (ref "U5") (pin "29") (pinfunction "PB5_29") (pintype "bidirectional"))
    )
    (net (code "99") (name "unconnected-(U5-PB6-Pad30)") (class "Default")
      (node (ref "U5") (pin "30") (pinfunction "PB6_30") (pintype "bidirectional"))
    )
    (net (code "100") (name "unconnected-(U5-PB7-Pad12)") (class "Default")
      (node (ref "U5") (pin "12") (pinfunction "PB7_12") (pintype "bidirectional"))
    )
    (net (code "101") (name "unconnected-(U5-PC6-Pad31)") (class "Default")
      (node (ref "U5") (pin "31") (pinfunction "PC6_31") (pintype "bidirectional"))
    )
    (net (code "102") (name "unconnected-(U5-PC7-Pad32)") (class "Default")
      (node (ref "U5") (pin "32") (pinfunction "PC7_32") (pintype "bidirectional"))
    )
    (net (code "103") (name "unconnected-(U5-PD3-Pad21)") (class "Default")
      (node (ref "U5") (pin "21") (pinfunction "PD3_21") (pintype "bidirectional"))
    )
    (net (code "104") (name "unconnected-(U5-PD4-Pad25)") (class "Default")
      (node (ref "U5") (pin "25") (pinfunction "PD4_25") (pintype "bidirectional"))
    )
    (net (code "105") (name "unconnected-(U5-PD5-Pad22)") (class "Default")
      (node (ref "U5") (pin "22") (pinfunction "PD5_22") (pintype "bidirectional"))
    )
    (net (code "106") (name "unconnected-(U5-PD6-Pad26)") (class "Default")
      (node (ref "U5") (pin "26") (pinfunction "PD6_26") (pintype "bidirectional"))
    )
    (net (code "107") (name "unconnected-(U5-PD7-Pad27)") (class "Default")
      (node (ref "U5") (pin "27") (pinfunction "PD7_27") (pintype "bidirectional"))
    )
    (net (code "108") (name "unconnected-(U5-PE2-Pad33)") (class "Default")
      (node (ref "U5") (pin "33") (pinfunction "PE2_33") (pintype "bidirectional"))
    )
    (net (code "109") (name "unconnected-(U5-PE6-Pad1)") (class "Default")
      (node (ref "U5") (pin "1") (pinfunction "PE6_1") (pintype "bidirectional"))
    )
    (net (code "110") (name "unconnected-(U5-PF0-Pad41)") (class "Default")
      (node (ref "U5") (pin "41") (pinfunction "PF0_41") (pintype "bidirectional"))
    )
    (net (code "111") (name "unconnected-(U5-PF1-Pad40)") (class "Default")
      (node (ref "U5") (pin "40") (pinfunction "PF1_40") (pintype "bidirectional"))
    )
    (net (code "112") (name "unconnected-(U5-PF4-Pad39)") (class "Default")
      (node (ref "U5") (pin "39") (pinfunction "PF4_39") (pintype "bidirectional"))
    )
    (net (code "113") (name "unconnected-(U5-PF5-Pad38)") (class "Default")
      (node (ref "U5") (pin "38") (pinfunction "PF5_38") (pintype "bidirectional"))
    )
    (net (code "114") (name "unconnected-(U5-PF7-Pad36)") (class "Default")
      (node (ref "U5") (pin "36") (pinfunction "PF7_36") (pintype "bidirectional"))
    )
    (net (code "115") (name "unconnected-(X2-Pad2)") (class "Default")
      (node (ref "X2") (pin "2") (pinfunction "2_2") (pintype "passive"))
    )
    (net (code "116") (name "unconnected-(X2-Pad4)") (class "Default")
      (node (ref "X2") (pin "4") (pinfunction "4_4") (pintype "passive"))
    )
    (net (code "117") (name "unconnected-(X3-Pad2)") (class "Default")
      (node (ref "X3") (pin "2") (pinfunction "2_2") (pintype "passive"))
    )
    (net (code "118") (name "unconnected-(X3-Pad4)") (class "Default")
      (node (ref "X3") (pin "4") (pinfunction "4_4") (pintype "passive"))
    )
  )
)
